# Breakouts2.net
KiCad netlist of a schematic drawn in EAGLE
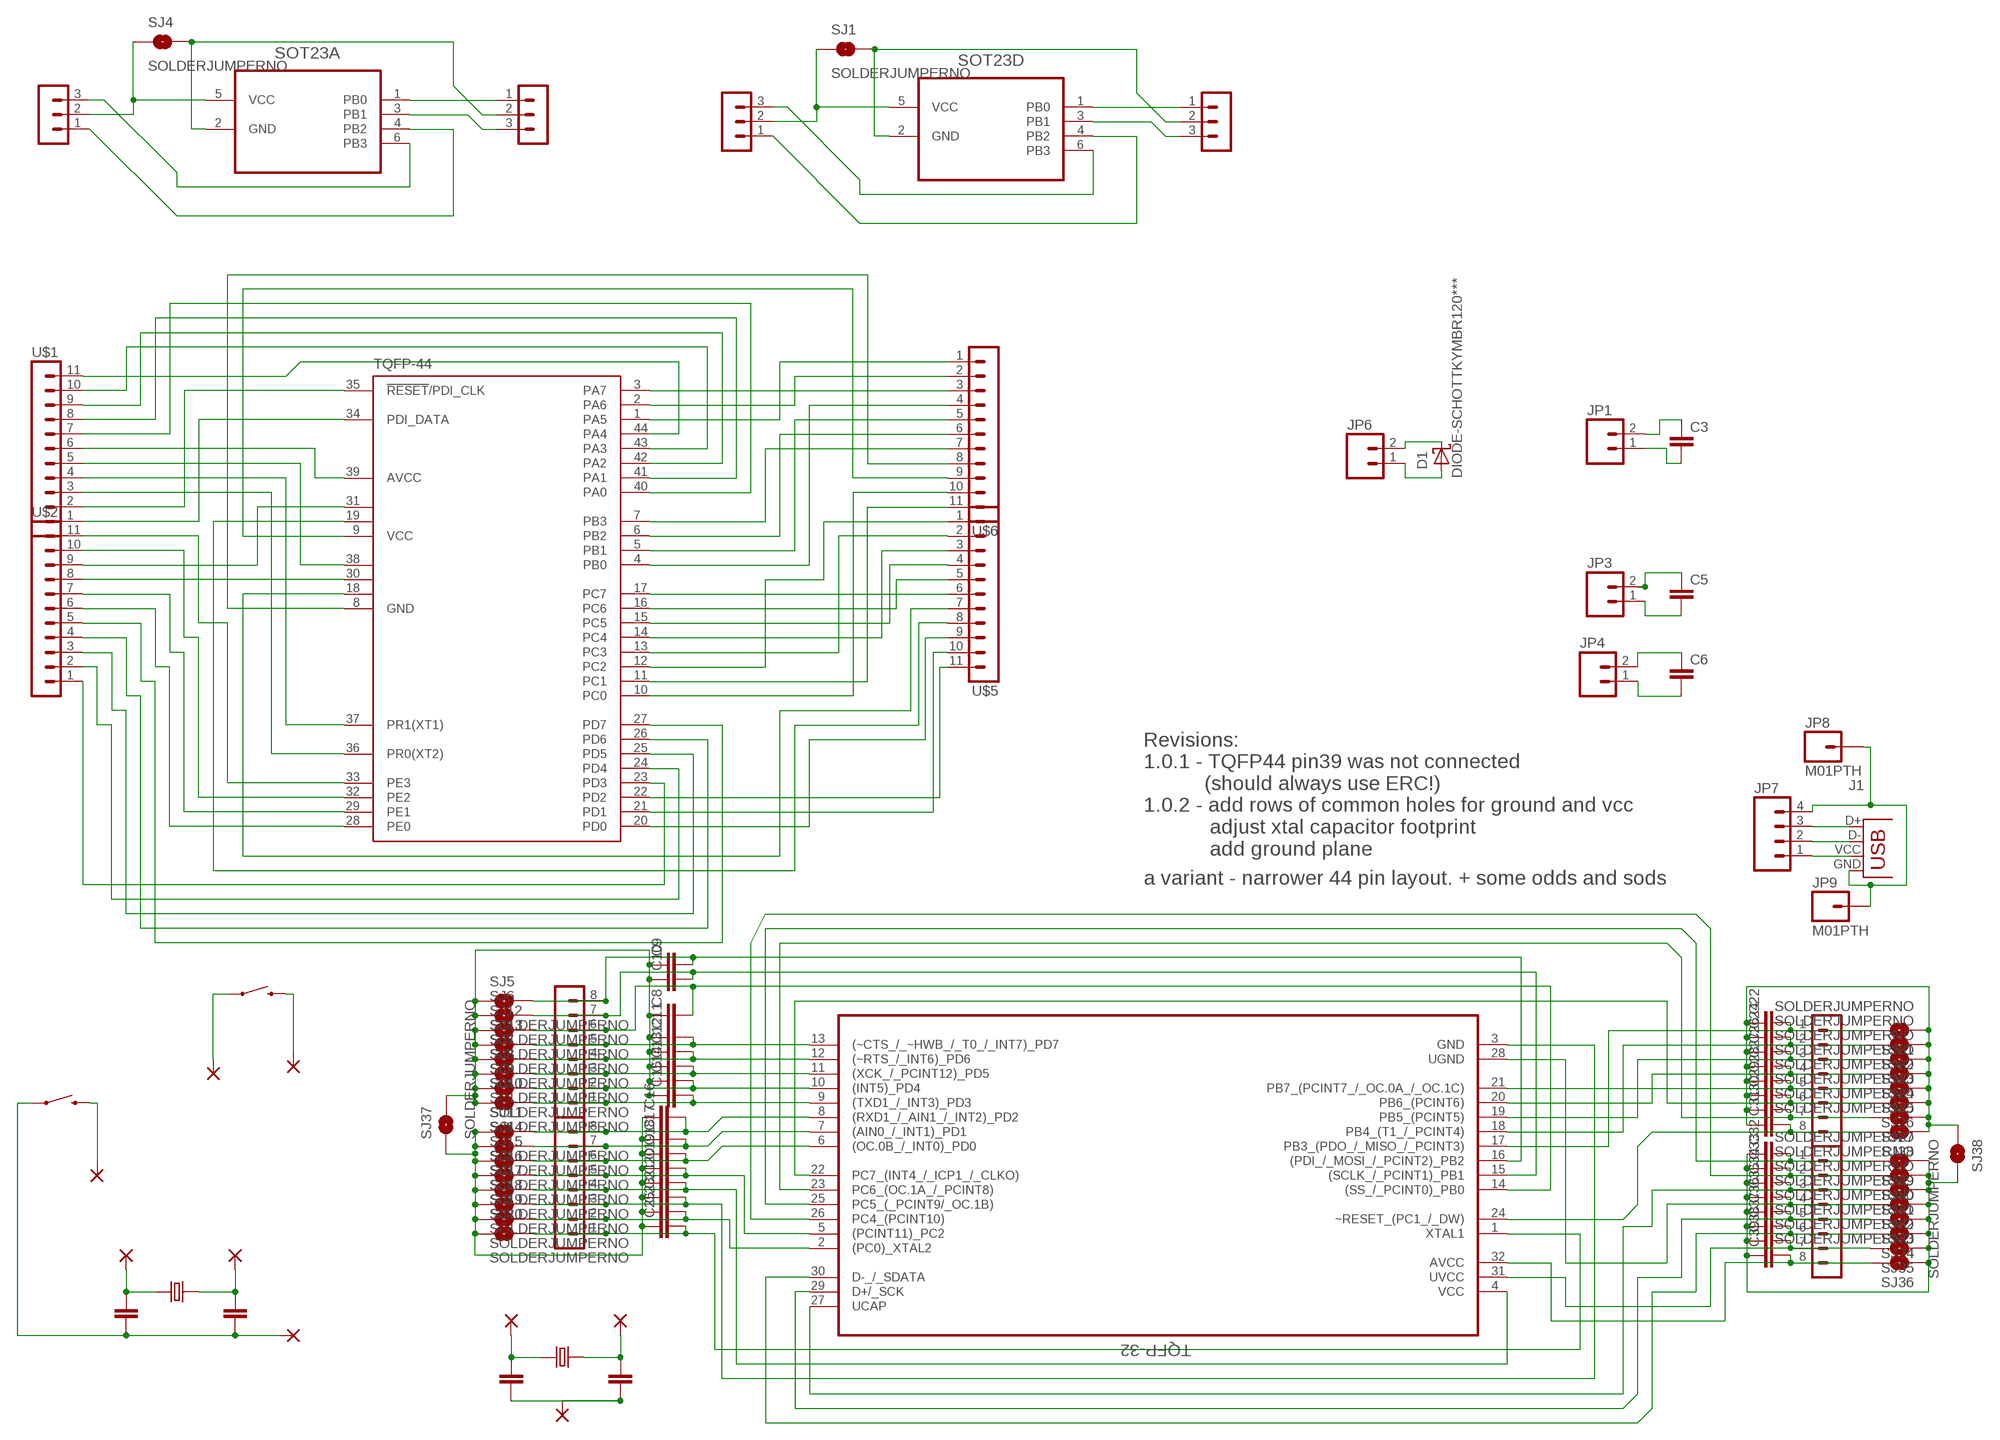
[diagram p0: schematic, sheet 1]

(export (version "E")
  (design (tool "Eeschema 10.0.6"))
  (components
    (comp (ref "C1")
      (value "C-EU025-024X044**100NF+22PF")
      (footprint "eagle-import:C025-024X044")
      (libsource (lib "eagle-import") (part "C-EU025-024X044100NF+22PF"))
    )
    (comp (ref "C2")
      (value "C-EU025-024X044**100NF+22PF")
      (footprint "eagle-import:C025-024X044")
      (libsource (lib "eagle-import") (part "C-EU025-024X044100NF+22PF"))
    )
    (comp (ref "C3")
      (value "C-EU1206")
      (footprint "eagle-import:1206")
      (libsource (lib "eagle-import") (part "C-EU1206"))
    )
    (comp (ref "C5")
      (value "C-EU1206")
      (footprint "eagle-import:1206")
      (libsource (lib "eagle-import") (part "C-EU1206"))
    )
    (comp (ref "C6")
      (value "C-EU1206")
      (footprint "eagle-import:1206")
      (libsource (lib "eagle-import") (part "C-EU1206"))
    )
    (comp (ref "C8")
      (value "C-EU1206")
      (footprint "eagle-import:1206")
      (libsource (lib "eagle-import") (part "C-EU1206"))
    )
    (comp (ref "C9")
      (value "C-EU1206")
      (footprint "eagle-import:1206")
      (libsource (lib "eagle-import") (part "C-EU1206"))
    )
    (comp (ref "C10")
      (value "C-EU1206")
      (footprint "eagle-import:1206")
      (libsource (lib "eagle-import") (part "C-EU1206"))
    )
    (comp (ref "C11")
      (value "C-EU1206")
      (footprint "eagle-import:1206")
      (libsource (lib "eagle-import") (part "C-EU1206"))
    )
    (comp (ref "C12")
      (value "C-EU1206")
      (footprint "eagle-import:1206")
      (libsource (lib "eagle-import") (part "C-EU1206"))
    )
    (comp (ref "C13")
      (value "C-EU1206")
      (footprint "eagle-import:1206")
      (libsource (lib "eagle-import") (part "C-EU1206"))
    )
    (comp (ref "C14")
      (value "C-EU1206")
      (footprint "eagle-import:1206")
      (libsource (lib "eagle-import") (part "C-EU1206"))
    )
    (comp (ref "C15")
      (value "C-EU1206")
      (footprint "eagle-import:1206")
      (libsource (lib "eagle-import") (part "C-EU1206"))
    )
    (comp (ref "C16")
      (value "C-EU1206")
      (footprint "eagle-import:1206")
      (libsource (lib "eagle-import") (part "C-EU1206"))
    )
    (comp (ref "C17")
      (value "C-EU1206")
      (footprint "eagle-import:1206")
      (libsource (lib "eagle-import") (part "C-EU1206"))
    )
    (comp (ref "C18")
      (value "C-EU1206")
      (footprint "eagle-import:1206")
      (libsource (lib "eagle-import") (part "C-EU1206"))
    )
    (comp (ref "C19")
      (value "C-EU1206")
      (footprint "eagle-import:1206")
      (libsource (lib "eagle-import") (part "C-EU1206"))
    )
    (comp (ref "C20")
      (value "C-EU1206")
      (footprint "eagle-import:1206")
      (libsource (lib "eagle-import") (part "C-EU1206"))
    )
    (comp (ref "C21")
      (value "C-EU1206")
      (footprint "eagle-import:1206")
      (libsource (lib "eagle-import") (part "C-EU1206"))
    )
    (comp (ref "C22")
      (value "C-EU1206")
      (footprint "eagle-import:1206")
      (libsource (lib "eagle-import") (part "C-EU1206"))
    )
    (comp (ref "C23")
      (value "C-EU1206")
      (footprint "eagle-import:1206")
      (libsource (lib "eagle-import") (part "C-EU1206"))
    )
    (comp (ref "C24")
      (value "C-EU1206")
      (footprint "eagle-import:1206")
      (libsource (lib "eagle-import") (part "C-EU1206"))
    )
    (comp (ref "C25")
      (value "C-EU1206")
      (footprint "eagle-import:1206")
      (libsource (lib "eagle-import") (part "C-EU1206"))
    )
    (comp (ref "C26")
      (value "C-EU1206")
      (footprint "eagle-import:1206")
      (libsource (lib "eagle-import") (part "C-EU1206"))
    )
    (comp (ref "C27")
      (value "C-EU1206")
      (footprint "eagle-import:1206")
      (libsource (lib "eagle-import") (part "C-EU1206"))
    )
    (comp (ref "C28")
      (value "C-EU1206")
      (footprint "eagle-import:1206")
      (libsource (lib "eagle-import") (part "C-EU1206"))
    )
    (comp (ref "C29")
      (value "C-EU1206")
      (footprint "eagle-import:1206")
      (libsource (lib "eagle-import") (part "C-EU1206"))
    )
    (comp (ref "C30")
      (value "C-EU1206")
      (footprint "eagle-import:1206")
      (libsource (lib "eagle-import") (part "C-EU1206"))
    )
    (comp (ref "C31")
      (value "C-EU1206")
      (footprint "eagle-import:1206")
      (libsource (lib "eagle-import") (part "C-EU1206"))
    )
    (comp (ref "C32")
      (value "C-EU1206")
      (footprint "eagle-import:1206")
      (libsource (lib "eagle-import") (part "C-EU1206"))
    )
    (comp (ref "C33")
      (value "C-EU1206")
      (footprint "eagle-import:1206")
      (libsource (lib "eagle-import") (part "C-EU1206"))
    )
    (comp (ref "C34")
      (value "C-EU1206")
      (footprint "eagle-import:1206")
      (libsource (lib "eagle-import") (part "C-EU1206"))
    )
    (comp (ref "C35")
      (value "C-EU1206")
      (footprint "eagle-import:1206")
      (libsource (lib "eagle-import") (part "C-EU1206"))
    )
    (comp (ref "C36")
      (value "C-EU1206")
      (footprint "eagle-import:1206")
      (libsource (lib "eagle-import") (part "C-EU1206"))
    )
    (comp (ref "C37")
      (value "C-EU1206")
      (footprint "eagle-import:1206")
      (libsource (lib "eagle-import") (part "C-EU1206"))
    )
    (comp (ref "C38")
      (value "C-EU1206")
      (footprint "eagle-import:1206")
      (libsource (lib "eagle-import") (part "C-EU1206"))
    )
    (comp (ref "C39")
      (value "C-EU1206")
      (footprint "eagle-import:1206")
      (libsource (lib "eagle-import") (part "C-EU1206"))
    )
    (comp (ref "C40")
      (value "C-EU025-024X044**100NF+22PF")
      (footprint "eagle-import:C025-024X044")
      (libsource (lib "eagle-import") (part "C-EU025-024X044100NF+22PF"))
    )
    (comp (ref "C41")
      (value "C-EU025-024X044**100NF+22PF")
      (footprint "eagle-import:C025-024X044")
      (libsource (lib "eagle-import") (part "C-EU025-024X044100NF+22PF"))
    )
    (comp (ref "D1")
      (value "DIODE-SCHOTTKYMBR120***")
      (footprint "eagle-import:SOD123")
      (libsource (lib "eagle-import") (part "DIODE-SCHOTTKYMBR120"))
    )
    (comp (ref "J1")
      (value "USB-FCI_SMD***")
      (footprint "eagle-import:FCI_USB_B_SMD")
      (libsource (lib "eagle-import") (part "USB-FCI_SMD"))
    )
    (comp (ref "JP1")
      (value "M02PTH")
      (footprint "eagle-import:1X02")
      (libsource (lib "eagle-import") (part "M02PTH"))
    )
    (comp (ref "JP3")
      (value "M02PTH")
      (footprint "eagle-import:1X02")
      (libsource (lib "eagle-import") (part "M02PTH"))
    )
    (comp (ref "JP4")
      (value "M02PTH")
      (footprint "eagle-import:1X02")
      (libsource (lib "eagle-import") (part "M02PTH"))
    )
    (comp (ref "JP6")
      (value "M02PTH")
      (footprint "eagle-import:1X02")
      (libsource (lib "eagle-import") (part "M02PTH"))
    )
    (comp (ref "JP7")
      (value "M04PTH")
      (footprint "eagle-import:1X04")
      (libsource (lib "eagle-import") (part "M04PTH"))
    )
    (comp (ref "JP8")
      (value "M01PTH")
      (footprint "eagle-import:1X01")
      (libsource (lib "eagle-import") (part "M01PTH"))
    )
    (comp (ref "JP9")
      (value "M01PTH")
      (footprint "eagle-import:1X01")
      (libsource (lib "eagle-import") (part "M01PTH"))
    )
    (comp (ref "PAD1")
      (value "WIREPAD1,6/0,8")
      (footprint "eagle-import:1,6_0,8")
      (libsource (lib "eagle-import") (part "WIREPAD1,6/0,8"))
    )
    (comp (ref "PAD2")
      (value "WIREPAD1,6/0,8")
      (footprint "eagle-import:1,6_0,8")
      (libsource (lib "eagle-import") (part "WIREPAD1,6/0,8"))
    )
    (comp (ref "PAD3")
      (value "WIREPAD1,6/0,8")
      (footprint "eagle-import:1,6_0,8")
      (libsource (lib "eagle-import") (part "WIREPAD1,6/0,8"))
    )
    (comp (ref "PAD4")
      (value "WIREPAD1,6/0,8")
      (footprint "eagle-import:1,6_0,8")
      (libsource (lib "eagle-import") (part "WIREPAD1,6/0,8"))
    )
    (comp (ref "PAD5")
      (value "WIREPAD1,6/0,8")
      (footprint "eagle-import:1,6_0,8")
      (libsource (lib "eagle-import") (part "WIREPAD1,6/0,8"))
    )
    (comp (ref "PAD6")
      (value "WIREPAD1,6/0,8")
      (footprint "eagle-import:1,6_0,8")
      (libsource (lib "eagle-import") (part "WIREPAD1,6/0,8"))
    )
    (comp (ref "PAD7")
      (value "WIREPAD1,6/0,8")
      (footprint "eagle-import:1,6_0,8")
      (libsource (lib "eagle-import") (part "WIREPAD1,6/0,8"))
    )
    (comp (ref "PAD8")
      (value "WIREPAD1,6/0,8")
      (footprint "eagle-import:1,6_0,8")
      (libsource (lib "eagle-import") (part "WIREPAD1,6/0,8"))
    )
    (comp (ref "PAD9")
      (value "WIREPAD1,6/0,8")
      (footprint "eagle-import:1,6_0,8")
      (libsource (lib "eagle-import") (part "WIREPAD1,6/0,8"))
    )
    (comp (ref "S1")
      (value "SWITCH-MOMENTARY-2PTH")
      (footprint "eagle-import:TACTILE-PTH")
      (libsource (lib "eagle-import") (part "SWITCH-MOMENTARY-2PTH"))
    )
    (comp (ref "S2")
      (value "SWITCH-MOMENTARY-2PTH")
      (footprint "eagle-import:TACTILE-PTH")
      (libsource (lib "eagle-import") (part "SWITCH-MOMENTARY-2PTH"))
    )
    (comp (ref "SJ1")
      (value "SOLDERJUMPERNO")
      (footprint "eagle-import:SJ_2S-NO")
      (libsource (lib "eagle-import") (part "SOLDERJUMPERNO"))
    )
    (comp (ref "SJ4")
      (value "SOLDERJUMPERNO")
      (footprint "eagle-import:SJ_2S-NO")
      (libsource (lib "eagle-import") (part "SOLDERJUMPERNO"))
    )
    (comp (ref "SJ5")
      (value "SOLDERJUMPERNO")
      (footprint "eagle-import:SJ_2S-NO")
      (libsource (lib "eagle-import") (part "SOLDERJUMPERNO"))
    )
    (comp (ref "SJ6")
      (value "SOLDERJUMPERNO")
      (footprint "eagle-import:SJ_2S-NO")
      (libsource (lib "eagle-import") (part "SOLDERJUMPERNO"))
    )
    (comp (ref "SJ7")
      (value "SOLDERJUMPERNO")
      (footprint "eagle-import:SJ_2S-NO")
      (libsource (lib "eagle-import") (part "SOLDERJUMPERNO"))
    )
    (comp (ref "SJ8")
      (value "SOLDERJUMPERNO")
      (footprint "eagle-import:SJ_2S-NO")
      (libsource (lib "eagle-import") (part "SOLDERJUMPERNO"))
    )
    (comp (ref "SJ9")
      (value "SOLDERJUMPERNO")
      (footprint "eagle-import:SJ_2S-NO")
      (libsource (lib "eagle-import") (part "SOLDERJUMPERNO"))
    )
    (comp (ref "SJ10")
      (value "SOLDERJUMPERNO")
      (footprint "eagle-import:SJ_2S-NO")
      (libsource (lib "eagle-import") (part "SOLDERJUMPERNO"))
    )
    (comp (ref "SJ11")
      (value "SOLDERJUMPERNO")
      (footprint "eagle-import:SJ_2S-NO")
      (libsource (lib "eagle-import") (part "SOLDERJUMPERNO"))
    )
    (comp (ref "SJ12")
      (value "SOLDERJUMPERNO")
      (footprint "eagle-import:SJ_2S-NO")
      (libsource (lib "eagle-import") (part "SOLDERJUMPERNO"))
    )
    (comp (ref "SJ13")
      (value "SOLDERJUMPERNO")
      (footprint "eagle-import:SJ_2S-NO")
      (libsource (lib "eagle-import") (part "SOLDERJUMPERNO"))
    )
    (comp (ref "SJ14")
      (value "SOLDERJUMPERNO")
      (footprint "eagle-import:SJ_2S-NO")
      (libsource (lib "eagle-import") (part "SOLDERJUMPERNO"))
    )
    (comp (ref "SJ15")
      (value "SOLDERJUMPERNO")
      (footprint "eagle-import:SJ_2S-NO")
      (libsource (lib "eagle-import") (part "SOLDERJUMPERNO"))
    )
    (comp (ref "SJ16")
      (value "SOLDERJUMPERNO")
      (footprint "eagle-import:SJ_2S-NO")
      (libsource (lib "eagle-import") (part "SOLDERJUMPERNO"))
    )
    (comp (ref "SJ17")
      (value "SOLDERJUMPERNO")
      (footprint "eagle-import:SJ_2S-NO")
      (libsource (lib "eagle-import") (part "SOLDERJUMPERNO"))
    )
    (comp (ref "SJ18")
      (value "SOLDERJUMPERNO")
      (footprint "eagle-import:SJ_2S-NO")
      (libsource (lib "eagle-import") (part "SOLDERJUMPERNO"))
    )
    (comp (ref "SJ19")
      (value "SOLDERJUMPERNO")
      (footprint "eagle-import:SJ_2S-NO")
      (libsource (lib "eagle-import") (part "SOLDERJUMPERNO"))
    )
    (comp (ref "SJ20")
      (value "SOLDERJUMPERNO")
      (footprint "eagle-import:SJ_2S-NO")
      (libsource (lib "eagle-import") (part "SOLDERJUMPERNO"))
    )
    (comp (ref "SJ21")
      (value "SOLDERJUMPERNO")
      (footprint "eagle-import:SJ_2S-NO")
      (libsource (lib "eagle-import") (part "SOLDERJUMPERNO"))
    )
    (comp (ref "SJ22")
      (value "SOLDERJUMPERNO")
      (footprint "eagle-import:SJ_2S-NO")
      (libsource (lib "eagle-import") (part "SOLDERJUMPERNO"))
    )
    (comp (ref "SJ23")
      (value "SOLDERJUMPERNO")
      (footprint "eagle-import:SJ_2S-NO")
      (libsource (lib "eagle-import") (part "SOLDERJUMPERNO"))
    )
    (comp (ref "SJ24")
      (value "SOLDERJUMPERNO")
      (footprint "eagle-import:SJ_2S-NO")
      (libsource (lib "eagle-import") (part "SOLDERJUMPERNO"))
    )
    (comp (ref "SJ25")
      (value "SOLDERJUMPERNO")
      (footprint "eagle-import:SJ_2S-NO")
      (libsource (lib "eagle-import") (part "SOLDERJUMPERNO"))
    )
    (comp (ref "SJ26")
      (value "SOLDERJUMPERNO")
      (footprint "eagle-import:SJ_2S-NO")
      (libsource (lib "eagle-import") (part "SOLDERJUMPERNO"))
    )
    (comp (ref "SJ27")
      (value "SOLDERJUMPERNO")
      (footprint "eagle-import:SJ_2S-NO")
      (libsource (lib "eagle-import") (part "SOLDERJUMPERNO"))
    )
    (comp (ref "SJ28")
      (value "SOLDERJUMPERNO")
      (footprint "eagle-import:SJ_2S-NO")
      (libsource (lib "eagle-import") (part "SOLDERJUMPERNO"))
    )
    (comp (ref "SJ29")
      (value "SOLDERJUMPERNO")
      (footprint "eagle-import:SJ_2S-NO")
      (libsource (lib "eagle-import") (part "SOLDERJUMPERNO"))
    )
    (comp (ref "SJ30")
      (value "SOLDERJUMPERNO")
      (footprint "eagle-import:SJ_2S-NO")
      (libsource (lib "eagle-import") (part "SOLDERJUMPERNO"))
    )
    (comp (ref "SJ31")
      (value "SOLDERJUMPERNO")
      (footprint "eagle-import:SJ_2S-NO")
      (libsource (lib "eagle-import") (part "SOLDERJUMPERNO"))
    )
    (comp (ref "SJ32")
      (value "SOLDERJUMPERNO")
      (footprint "eagle-import:SJ_2S-NO")
      (libsource (lib "eagle-import") (part "SOLDERJUMPERNO"))
    )
    (comp (ref "SJ33")
      (value "SOLDERJUMPERNO")
      (footprint "eagle-import:SJ_2S-NO")
      (libsource (lib "eagle-import") (part "SOLDERJUMPERNO"))
    )
    (comp (ref "SJ34")
      (value "SOLDERJUMPERNO")
      (footprint "eagle-import:SJ_2S-NO")
      (libsource (lib "eagle-import") (part "SOLDERJUMPERNO"))
    )
    (comp (ref "SJ35")
      (value "SOLDERJUMPERNO")
      (footprint "eagle-import:SJ_2S-NO")
      (libsource (lib "eagle-import") (part "SOLDERJUMPERNO"))
    )
    (comp (ref "SJ36")
      (value "SOLDERJUMPERNO")
      (footprint "eagle-import:SJ_2S-NO")
      (libsource (lib "eagle-import") (part "SOLDERJUMPERNO"))
    )
    (comp (ref "SJ37")
      (value "SOLDERJUMPERNO")
      (footprint "eagle-import:SJ_2S-NO")
      (libsource (lib "eagle-import") (part "SOLDERJUMPERNO"))
    )
    (comp (ref "SJ38")
      (value "SOLDERJUMPERNO")
      (footprint "eagle-import:SJ_2S-NO")
      (libsource (lib "eagle-import") (part "SOLDERJUMPERNO"))
    )
    (comp (ref "SOT23A")
      (value "ATTINY10-TSHR")
      (footprint "eagle-import:SOT95P280X145-6N")
      (libsource (lib "eagle-import") (part "ATTINY10-TSHR"))
    )
    (comp (ref "SOT23D")
      (value "ATTINY10-TSHR")
      (footprint "eagle-import:SOT95P280X145-6N")
      (libsource (lib "eagle-import") (part "ATTINY10-TSHR"))
    )
    (comp (ref "SV4")
      (value "MA08-1")
      (footprint "eagle-import:MA08-1")
      (libsource (lib "eagle-import") (part "MA08-1"))
    )
    (comp (ref "SV8")
      (value "MA08-1")
      (footprint "eagle-import:MA08-1")
      (libsource (lib "eagle-import") (part "MA08-1"))
    )
    (comp (ref "SV12")
      (value "MA03-1")
      (footprint "eagle-import:MA03-1")
      (libsource (lib "eagle-import") (part "MA03-1"))
    )
    (comp (ref "SV13")
      (value "MA03-1")
      (footprint "eagle-import:MA03-1")
      (libsource (lib "eagle-import") (part "MA03-1"))
    )
    (comp (ref "SV14")
      (value "MA03-1")
      (footprint "eagle-import:MA03-1")
      (libsource (lib "eagle-import") (part "MA03-1"))
    )
    (comp (ref "SV15")
      (value "MA03-1")
      (footprint "eagle-import:MA03-1")
      (libsource (lib "eagle-import") (part "MA03-1"))
    )
    (comp (ref "SV16")
      (value "MA08-1")
      (footprint "eagle-import:MA08-1")
      (libsource (lib "eagle-import") (part "MA08-1"))
    )
    (comp (ref "SV18")
      (value "MA08-1")
      (footprint "eagle-import:MA08-1")
      (libsource (lib "eagle-import") (part "MA08-1"))
    )
    (comp (ref "TQFP-32")
      (value "AT90USB162-16AU")
      (footprint "eagle-import:QFP80P900X900X120-32N")
      (libsource (lib "eagle-import") (part "AT90USB162-16AU"))
    )
    (comp (ref "TQFP-44")
      (value "XMEGA16A4A")
      (footprint "eagle-import:TQFP44")
      (libsource (lib "eagle-import") (part "XMEGA16A4A"))
    )
    (comp (ref "U$1")
      (value "MA11-1")
      (footprint "eagle-import:MA11-1S")
      (libsource (lib "eagle-import") (part "MA11-1"))
    )
    (comp (ref "U$2")
      (value "MA11-1")
      (footprint "eagle-import:MA11-1S")
      (libsource (lib "eagle-import") (part "MA11-1"))
    )
    (comp (ref "U$5")
      (value "MA11-1")
      (footprint "eagle-import:MA11-1S")
      (libsource (lib "eagle-import") (part "MA11-1"))
    )
    (comp (ref "U$6")
      (value "MA11-1")
      (footprint "eagle-import:MA11-1S")
      (libsource (lib "eagle-import") (part "MA11-1"))
    )
    (comp (ref "X1")
      (value "CRYSTAL-HC49U-V**16MHZ")
      (footprint "eagle-import:HC49U-V")
      (libsource (lib "eagle-import") (part "CRYSTAL-HC49U-V16MHZ"))
    )
    (comp (ref "X2")
      (value "CRYSTAL-HC49U-V**16MHZ")
      (footprint "eagle-import:HC49U-V")
      (libsource (lib "eagle-import") (part "CRYSTAL-HC49U-V16MHZ"))
    )
  )
  (nets
    (net (code "1") (name "Net-(C3-Pad1)") (class "Default")
      (node (ref "C3") (pin "1") (pinfunction "1_1") (pintype "passive"))
      (node (ref "JP1") (pin "2") (pinfunction "2_2") (pintype "passive"))
    )
    (net (code "2") (name "Net-(C3-Pad2)") (class "Default")
      (node (ref "C3") (pin "2") (pinfunction "2_2") (pintype "passive"))
      (node (ref "JP1") (pin "1") (pinfunction "1_1") (pintype "passive"))
    )
    (net (code "3") (name "Net-(C5-Pad1)") (class "Default")
      (node (ref "C5") (pin "1") (pinfunction "1_1") (pintype "passive"))
      (node (ref "JP3") (pin "2") (pinfunction "2_2") (pintype "passive"))
    )
    (net (code "4") (name "Net-(C5-Pad2)") (class "Default")
      (node (ref "C5") (pin "2") (pinfunction "2_2") (pintype "passive"))
      (node (ref "JP3") (pin "1") (pinfunction "1_1") (pintype "passive"))
    )
    (net (code "5") (name "Net-(C6-Pad1)") (class "Default")
      (node (ref "C6") (pin "1") (pinfunction "1_1") (pintype "passive"))
      (node (ref "JP4") (pin "2") (pinfunction "2_2") (pintype "passive"))
    )
    (net (code "6") (name "Net-(C6-Pad2)") (class "Default")
      (node (ref "C6") (pin "2") (pinfunction "2_2") (pintype "passive"))
      (node (ref "JP4") (pin "1") (pinfunction "1_1") (pintype "passive"))
    )
    (net (code "7") (name "Net-(C10-Pad1)") (class "Default")
      (node (ref "C10") (pin "1") (pinfunction "1_1") (pintype "passive"))
      (node (ref "C11") (pin "1") (pinfunction "1_1") (pintype "passive"))
      (node (ref "C12") (pin "1") (pinfunction "1_1") (pintype "passive"))
      (node (ref "C13") (pin "1") (pinfunction "1_1") (pintype "passive"))
      (node (ref "C14") (pin "1") (pinfunction "1_1") (pintype "passive"))
      (node (ref "C15") (pin "1") (pinfunction "1_1") (pintype "passive"))
      (node (ref "C8") (pin "1") (pinfunction "1_1") (pintype "passive"))
      (node (ref "C9") (pin "1") (pinfunction "1_1") (pintype "passive"))
      (node (ref "SJ10") (pin "1") (pinfunction "1_1") (pintype "passive"))
      (node (ref "SJ12") (pin "1") (pinfunction "1_1") (pintype "passive"))
      (node (ref "SJ13") (pin "1") (pinfunction "1_1") (pintype "passive"))
      (node (ref "SJ37") (pin "2") (pinfunction "2_2") (pintype "passive"))
      (node (ref "SJ5") (pin "1") (pinfunction "1_1") (pintype "passive"))
      (node (ref "SJ6") (pin "1") (pinfunction "1_1") (pintype "passive"))
      (node (ref "SJ7") (pin "1") (pinfunction "1_1") (pintype "passive"))
      (node (ref "SJ8") (pin "1") (pinfunction "1_1") (pintype "passive"))
      (node (ref "SJ9") (pin "1") (pinfunction "1_1") (pintype "passive"))
    )
    (net (code "8") (name "Net-(C16-Pad1)") (class "Default")
      (node (ref "C16") (pin "1") (pinfunction "1_1") (pintype "passive"))
      (node (ref "C17") (pin "1") (pinfunction "1_1") (pintype "passive"))
      (node (ref "C18") (pin "1") (pinfunction "1_1") (pintype "passive"))
      (node (ref "C19") (pin "1") (pinfunction "1_1") (pintype "passive"))
      (node (ref "C20") (pin "1") (pinfunction "1_1") (pintype "passive"))
      (node (ref "C21") (pin "1") (pinfunction "1_1") (pintype "passive"))
      (node (ref "C23") (pin "1") (pinfunction "1_1") (pintype "passive"))
      (node (ref "C25") (pin "1") (pinfunction "1_1") (pintype "passive"))
      (node (ref "SJ11") (pin "1") (pinfunction "1_1") (pintype "passive"))
      (node (ref "SJ14") (pin "1") (pinfunction "1_1") (pintype "passive"))
      (node (ref "SJ15") (pin "1") (pinfunction "1_1") (pintype "passive"))
      (node (ref "SJ16") (pin "1") (pinfunction "1_1") (pintype "passive"))
      (node (ref "SJ17") (pin "1") (pinfunction "1_1") (pintype "passive"))
      (node (ref "SJ18") (pin "1") (pinfunction "1_1") (pintype "passive"))
      (node (ref "SJ19") (pin "1") (pinfunction "1_1") (pintype "passive"))
      (node (ref "SJ20") (pin "1") (pinfunction "1_1") (pintype "passive"))
      (node (ref "SJ37") (pin "1") (pinfunction "1_1") (pintype "passive"))
    )
    (net (code "9") (name "Net-(C22-Pad1)") (class "Default")
      (node (ref "C22") (pin "1") (pinfunction "1_1") (pintype "passive"))
      (node (ref "C24") (pin "1") (pinfunction "1_1") (pintype "passive"))
      (node (ref "C26") (pin "1") (pinfunction "1_1") (pintype "passive"))
      (node (ref "C27") (pin "1") (pinfunction "1_1") (pintype "passive"))
      (node (ref "C28") (pin "1") (pinfunction "1_1") (pintype "passive"))
      (node (ref "C29") (pin "1") (pinfunction "1_1") (pintype "passive"))
      (node (ref "C30") (pin "1") (pinfunction "1_1") (pintype "passive"))
      (node (ref "C31") (pin "1") (pinfunction "1_1") (pintype "passive"))
      (node (ref "SJ21") (pin "1") (pinfunction "1_1") (pintype "passive"))
      (node (ref "SJ22") (pin "1") (pinfunction "1_1") (pintype "passive"))
      (node (ref "SJ23") (pin "1") (pinfunction "1_1") (pintype "passive"))
      (node (ref "SJ24") (pin "1") (pinfunction "1_1") (pintype "passive"))
      (node (ref "SJ25") (pin "1") (pinfunction "1_1") (pintype "passive"))
      (node (ref "SJ26") (pin "1") (pinfunction "1_1") (pintype "passive"))
      (node (ref "SJ27") (pin "1") (pinfunction "1_1") (pintype "passive"))
      (node (ref "SJ28") (pin "1") (pinfunction "1_1") (pintype "passive"))
      (node (ref "SJ38") (pin "1") (pinfunction "1_1") (pintype "passive"))
    )
    (net (code "10") (name "Net-(C32-Pad1)") (class "Default")
      (node (ref "C32") (pin "1") (pinfunction "1_1") (pintype "passive"))
      (node (ref "C33") (pin "1") (pinfunction "1_1") (pintype "passive"))
      (node (ref "C34") (pin "1") (pinfunction "1_1") (pintype "passive"))
      (node (ref "C35") (pin "1") (pinfunction "1_1") (pintype "passive"))
      (node (ref "C36") (pin "1") (pinfunction "1_1") (pintype "passive"))
      (node (ref "C37") (pin "1") (pinfunction "1_1") (pintype "passive"))
      (node (ref "C38") (pin "1") (pinfunction "1_1") (pintype "passive"))
      (node (ref "C39") (pin "1") (pinfunction "1_1") (pintype "passive"))
      (node (ref "SJ29") (pin "1") (pinfunction "1_1") (pintype "passive"))
      (node (ref "SJ30") (pin "1") (pinfunction "1_1") (pintype "passive"))
      (node (ref "SJ31") (pin "1") (pinfunction "1_1") (pintype "passive"))
      (node (ref "SJ32") (pin "1") (pinfunction "1_1") (pintype "passive"))
      (node (ref "SJ33") (pin "1") (pinfunction "1_1") (pintype "passive"))
      (node (ref "SJ34") (pin "1") (pinfunction "1_1") (pintype "passive"))
      (node (ref "SJ35") (pin "1") (pinfunction "1_1") (pintype "passive"))
      (node (ref "SJ36") (pin "1") (pinfunction "1_1") (pintype "passive"))
      (node (ref "SJ38") (pin "2") (pinfunction "2_2") (pintype "passive"))
    )
    (net (code "11") (name "Net-(D1-C)") (class "Default")
      (node (ref "D1") (pin "K") (pinfunction "C_K") (pintype "passive"))
      (node (ref "JP6") (pin "2") (pinfunction "2_2") (pintype "passive"))
    )
    (net (code "12") (name "Net-(D1-PadA)") (class "Default")
      (node (ref "D1") (pin "A") (pinfunction "A_A") (pintype "passive"))
      (node (ref "JP6") (pin "1") (pinfunction "1_1") (pintype "passive"))
    )
    (net (code "13") (name "Net-(J1-PadD+)") (class "Default")
      (node (ref "J1") (pin "D+") (pinfunction "D+_D+") (pintype "bidirectional"))
      (node (ref "JP7") (pin "3") (pinfunction "3_3") (pintype "passive"))
    )
    (net (code "14") (name "Net-(J1-PadD-)") (class "Default")
      (node (ref "J1") (pin "D-") (pinfunction "D-_D-") (pintype "bidirectional"))
      (node (ref "JP7") (pin "2") (pinfunction "2_2") (pintype "passive"))
    )
    (net (code "15") (name "Net-(J1-PadGND)") (class "Default")
      (node (ref "J1") (pin "GND") (pinfunction "GND_GND") (pintype "bidirectional"))
      (node (ref "JP7") (pin "4") (pinfunction "4_4") (pintype "passive"))
      (node (ref "JP8") (pin "1") (pinfunction "1_1") (pintype "passive"))
      (node (ref "JP9") (pin "1") (pinfunction "1_1") (pintype "passive"))
    )
    (net (code "16") (name "Net-(J1-VBUS)") (class "Default")
      (node (ref "J1") (pin "VCC") (pinfunction "VBUS_VCC") (pintype "bidirectional"))
      (node (ref "JP7") (pin "1") (pinfunction "1_1") (pintype "passive"))
    )
    (net (code "17") (name "Net-(PAD1-P)") (class "Default")
      (node (ref "PAD1") (pin "1") (pinfunction "P_1") (pintype "passive"))
      (node (ref "S1") (pin "3") (pinfunction "2_3") (pintype "passive"))
    )
    (net (code "18") (name "Net-(PAD2-P)") (class "Default")
      (node (ref "C41") (pin "1") (pinfunction "1_1") (pintype "passive"))
      (node (ref "PAD2") (pin "1") (pinfunction "P_1") (pintype "passive"))
      (node (ref "X2") (pin "1") (pinfunction "1_1") (pintype "passive"))
    )
    (net (code "19") (name "Net-(PAD3-P)") (class "Default")
      (node (ref "PAD3") (pin "1") (pinfunction "P_1") (pintype "passive"))
      (node (ref "S2") (pin "3") (pinfunction "2_3") (pintype "passive"))
    )
    (net (code "20") (name "Net-(PAD4-P)") (class "Default")
      (node (ref "PAD4") (pin "1") (pinfunction "P_1") (pintype "passive"))
      (node (ref "S2") (pin "1") (pinfunction "1_1") (pintype "passive"))
    )
    (net (code "21") (name "Net-(PAD5-P)") (class "Default")
      (node (ref "C40") (pin "1") (pinfunction "1_1") (pintype "passive"))
      (node (ref "PAD5") (pin "1") (pinfunction "P_1") (pintype "passive"))
      (node (ref "X2") (pin "2") (pinfunction "2_2") (pintype "passive"))
    )
    (net (code "22") (name "Net-(PAD6-P)") (class "Default")
      (node (ref "C2") (pin "1") (pinfunction "1_1") (pintype "passive"))
      (node (ref "PAD6") (pin "1") (pinfunction "P_1") (pintype "passive"))
      (node (ref "X1") (pin "1") (pinfunction "1_1") (pintype "passive"))
    )
    (net (code "23") (name "Net-(PAD7-P)") (class "Default")
      (node (ref "C1") (pin "1") (pinfunction "1_1") (pintype "passive"))
      (node (ref "PAD7") (pin "1") (pinfunction "P_1") (pintype "passive"))
      (node (ref "X1") (pin "2") (pinfunction "2_2") (pintype "passive"))
    )
    (net (code "24") (name "Net-(PAD8-P)") (class "Default")
      (node (ref "C1") (pin "2") (pinfunction "2_2") (pintype "passive"))
      (node (ref "C2") (pin "2") (pinfunction "2_2") (pintype "passive"))
      (node (ref "PAD8") (pin "1") (pinfunction "P_1") (pintype "passive"))
      (node (ref "S1") (pin "1") (pinfunction "1_1") (pintype "passive"))
    )
    (net (code "25") (name "Net-(PAD9-P)") (class "Default")
      (node (ref "C40") (pin "2") (pinfunction "2_2") (pintype "passive"))
      (node (ref "C41") (pin "2") (pinfunction "2_2") (pintype "passive"))
      (node (ref "PAD9") (pin "1") (pinfunction "P_1") (pintype "passive"))
    )
    (net (code "26") (name "Net-(SOT23A-GND)") (class "Default")
      (node (ref "SJ4") (pin "2") (pinfunction "2_2") (pintype "passive"))
      (node (ref "SOT23A") (pin "2") (pinfunction "GND_2") (pintype "passive"))
      (node (ref "SV15") (pin "2") (pinfunction "2_2") (pintype "passive"))
    )
    (net (code "27") (name "Net-(SOT23A-PB0)") (class "Default")
      (node (ref "SOT23A") (pin "1") (pinfunction "PB0_1") (pintype "bidirectional"))
      (node (ref "SV15") (pin "1") (pinfunction "1_1") (pintype "passive"))
    )
    (net (code "28") (name "Net-(SOT23A-PB1)") (class "Default")
      (node (ref "SOT23A") (pin "3") (pinfunction "PB1_3") (pintype "bidirectional"))
      (node (ref "SV15") (pin "3") (pinfunction "3_3") (pintype "passive"))
    )
    (net (code "29") (name "Net-(SOT23A-PB2)") (class "Default")
      (node (ref "SOT23A") (pin "4") (pinfunction "PB2_4") (pintype "bidirectional"))
      (node (ref "SV14") (pin "1") (pinfunction "1_1") (pintype "passive"))
    )
    (net (code "30") (name "Net-(SOT23A-PB3)") (class "Default")
      (node (ref "SOT23A") (pin "6") (pinfunction "PB3_6") (pintype "bidirectional"))
      (node (ref "SV14") (pin "3") (pinfunction "3_3") (pintype "passive"))
    )
    (net (code "31") (name "Net-(SOT23A-VCC)") (class "Default")
      (node (ref "SJ4") (pin "1") (pinfunction "1_1") (pintype "passive"))
      (node (ref "SOT23A") (pin "5") (pinfunction "VCC_5") (pintype "power_in"))
      (node (ref "SV14") (pin "2") (pinfunction "2_2") (pintype "passive"))
    )
    (net (code "32") (name "Net-(SOT23D-GND)") (class "Default")
      (node (ref "SJ1") (pin "2") (pinfunction "2_2") (pintype "passive"))
      (node (ref "SOT23D") (pin "2") (pinfunction "GND_2") (pintype "passive"))
      (node (ref "SV13") (pin "2") (pinfunction "2_2") (pintype "passive"))
    )
    (net (code "33") (name "Net-(SOT23D-PB0)") (class "Default")
      (node (ref "SOT23D") (pin "1") (pinfunction "PB0_1") (pintype "bidirectional"))
      (node (ref "SV13") (pin "1") (pinfunction "1_1") (pintype "passive"))
    )
    (net (code "34") (name "Net-(SOT23D-PB1)") (class "Default")
      (node (ref "SOT23D") (pin "3") (pinfunction "PB1_3") (pintype "bidirectional"))
      (node (ref "SV13") (pin "3") (pinfunction "3_3") (pintype "passive"))
    )
    (net (code "35") (name "Net-(SOT23D-PB2)") (class "Default")
      (node (ref "SOT23D") (pin "4") (pinfunction "PB2_4") (pintype "bidirectional"))
      (node (ref "SV12") (pin "1") (pinfunction "1_1") (pintype "passive"))
    )
    (net (code "36") (name "Net-(SOT23D-PB3)") (class "Default")
      (node (ref "SOT23D") (pin "6") (pinfunction "PB3_6") (pintype "bidirectional"))
      (node (ref "SV12") (pin "3") (pinfunction "3_3") (pintype "passive"))
    )
    (net (code "37") (name "Net-(SOT23D-VCC)") (class "Default")
      (node (ref "SJ1") (pin "1") (pinfunction "1_1") (pintype "passive"))
      (node (ref "SOT23D") (pin "5") (pinfunction "VCC_5") (pintype "power_in"))
      (node (ref "SV12") (pin "2") (pinfunction "2_2") (pintype "passive"))
    )
    (net (code "38") (name "Net-(TQFP-32-(AIN0_{slash}_INT1)_PD1)") (class "Default")
      (node (ref "C17") (pin "2") (pinfunction "2_2") (pintype "passive"))
      (node (ref "SJ14") (pin "2") (pinfunction "2_2") (pintype "passive"))
      (node (ref "SV16") (pin "7") (pinfunction "7_7") (pintype "passive"))
      (node (ref "TQFP-32") (pin "7") (pinfunction "(AIN0_/_INT1)_PD1_7") (pintype "bidirectional"))
    )
    (net (code "39") (name "Net-(TQFP-32-(INT5)_PD4)") (class "Default")
      (node (ref "C14") (pin "2") (pinfunction "2_2") (pintype "passive"))
      (node (ref "SJ9") (pin "2") (pinfunction "2_2") (pintype "passive"))
      (node (ref "SV18") (pin "2") (pinfunction "2_2") (pintype "passive"))
      (node (ref "TQFP-32") (pin "10") (pinfunction "(INT5)_PD4_10") (pintype "bidirectional"))
    )
    (net (code "40") (name "Net-(TQFP-32-(OC.0B_{slash}_INT0)_PD0)") (class "Default")
      (node (ref "C18") (pin "2") (pinfunction "2_2") (pintype "passive"))
      (node (ref "SJ15") (pin "2") (pinfunction "2_2") (pintype "passive"))
      (node (ref "SV16") (pin "6") (pinfunction "6_6") (pintype "passive"))
      (node (ref "TQFP-32") (pin "6") (pinfunction "(OC.0B_/_INT0)_PD0_6") (pintype "bidirectional"))
    )
    (net (code "41") (name "Net-(TQFP-32-(PC0)_XTAL2)") (class "Default")
      (node (ref "C23") (pin "2") (pinfunction "2_2") (pintype "passive"))
      (node (ref "SJ19") (pin "2") (pinfunction "2_2") (pintype "passive"))
      (node (ref "SV16") (pin "2") (pinfunction "2_2") (pintype "passive"))
      (node (ref "TQFP-32") (pin "2") (pinfunction "(PC0)_XTAL2_2") (pintype "bidirectional"))
    )
    (net (code "42") (name "Net-(TQFP-32-(PCINT11)_PC2)") (class "Default")
      (node (ref "C19") (pin "2") (pinfunction "2_2") (pintype "passive"))
      (node (ref "SJ16") (pin "2") (pinfunction "2_2") (pintype "passive"))
      (node (ref "SV16") (pin "5") (pinfunction "5_5") (pintype "passive"))
      (node (ref "TQFP-32") (pin "5") (pinfunction "(PCINT11)_PC2_5") (pintype "bidirectional"))
    )
    (net (code "43") (name "Net-(TQFP-32-(PDI_{slash}_MOSI_{slash}_PCINT2)_PB2)") (class "Default")
      (node (ref "C9") (pin "2") (pinfunction "2_2") (pintype "passive"))
      (node (ref "SJ5") (pin "2") (pinfunction "2_2") (pintype "passive"))
      (node (ref "SV18") (pin "8") (pinfunction "8_8") (pintype "passive"))
      (node (ref "TQFP-32") (pin "16") (pinfunction "(PDI_/_MOSI_/_PCINT2)_PB2_16") (pintype "bidirectional"))
    )
    (net (code "44") (name "Net-(TQFP-32-(RXD1_{slash}_AIN1_{slash}_INT2)_PD2)") (class "Default")
      (node (ref "C16") (pin "2") (pinfunction "2_2") (pintype "passive"))
      (node (ref "SJ11") (pin "2") (pinfunction "2_2") (pintype "passive"))
      (node (ref "SV16") (pin "8") (pinfunction "8_8") (pintype "passive"))
      (node (ref "TQFP-32") (pin "8") (pinfunction "(RXD1_/_AIN1_/_INT2)_PD2_8") (pintype "bidirectional"))
    )
    (net (code "45") (name "Net-(TQFP-32-(SCLK_{slash}_PCINT1)_PB1)") (class "Default")
      (node (ref "C10") (pin "2") (pinfunction "2_2") (pintype "passive"))
      (node (ref "SJ6") (pin "2") (pinfunction "2_2") (pintype "passive"))
      (node (ref "SV18") (pin "7") (pinfunction "7_7") (pintype "passive"))
      (node (ref "TQFP-32") (pin "15") (pinfunction "(SCLK_/_PCINT1)_PB1_15") (pintype "bidirectional"))
    )
    (net (code "46") (name "Net-(TQFP-32-(SS_{slash}_PCINT0)_PB0)") (class "Default")
      (node (ref "C8") (pin "2") (pinfunction "2_2") (pintype "passive"))
      (node (ref "SJ12") (pin "2") (pinfunction "2_2") (pintype "passive"))
      (node (ref "SV18") (pin "6") (pinfunction "6_6") (pintype "passive"))
      (node (ref "TQFP-32") (pin "14") (pinfunction "(SS_/_PCINT0)_PB0_14") (pintype "bidirectional"))
    )
    (net (code "47") (name "Net-(TQFP-32-(TXD1_{slash}_INT3)_PD3)") (class "Default")
      (node (ref "C15") (pin "2") (pinfunction "2_2") (pintype "passive"))
      (node (ref "SJ10") (pin "2") (pinfunction "2_2") (pintype "passive"))
      (node (ref "SV18") (pin "1") (pinfunction "1_1") (pintype "passive"))
      (node (ref "TQFP-32") (pin "9") (pinfunction "(TXD1_/_INT3)_PD3_9") (pintype "bidirectional"))
    )
    (net (code "48") (name "Net-(TQFP-32-(XCK_{slash}_PCINT12)_PD5)") (class "Default")
      (node (ref "C13") (pin "2") (pinfunction "2_2") (pintype "passive"))
      (node (ref "SJ8") (pin "2") (pinfunction "2_2") (pintype "passive"))
      (node (ref "SV18") (pin "3") (pinfunction "3_3") (pintype "passive"))
      (node (ref "TQFP-32") (pin "11") (pinfunction "(XCK_/_PCINT12)_PD5_11") (pintype "bidirectional"))
    )
    (net (code "49") (name "Net-(TQFP-32-(~{CTS_{slash}_}HWB_{slash}_T0_{slash}_INT7)_PD7)") (class "Default")
      (node (ref "C11") (pin "2") (pinfunction "2_2") (pintype "passive"))
      (node (ref "SJ13") (pin "2") (pinfunction "2_2") (pintype "passive"))
      (node (ref "SV18") (pin "5") (pinfunction "5_5") (pintype "passive"))
      (node (ref "TQFP-32") (pin "13") (pinfunction "(~{CTS_/_}HWB_/_T0_/_INT7)_PD7_13") (pintype "bidirectional"))
    )
    (net (code "50") (name "Net-(TQFP-32-(~{RTS_{slash}_INT6})_PD6)") (class "Default")
      (node (ref "C12") (pin "2") (pinfunction "2_2") (pintype "passive"))
      (node (ref "SJ7") (pin "2") (pinfunction "2_2") (pintype "passive"))
      (node (ref "SV18") (pin "4") (pinfunction "4_4") (pintype "passive"))
      (node (ref "TQFP-32") (pin "12") (pinfunction "(~{RTS_/_INT6})_PD6_12") (pintype "bidirectional"))
    )
    (net (code "51") (name "Net-(TQFP-32-AVCC)") (class "Default")
      (node (ref "C39") (pin "2") (pinfunction "2_2") (pintype "passive"))
      (node (ref "SJ36") (pin "2") (pinfunction "2_2") (pintype "passive"))
      (node (ref "SV8") (pin "8") (pinfunction "8_8") (pintype "passive"))
      (node (ref "TQFP-32") (pin "32") (pinfunction "AVCC_32") (pintype "power_in"))
    )
    (net (code "52") (name "Net-(TQFP-32-D+{slash}_SCK)") (class "Default")
      (node (ref "C36") (pin "2") (pinfunction "2_2") (pintype "passive"))
      (node (ref "SJ33") (pin "2") (pinfunction "2_2") (pintype "passive"))
      (node (ref "SV8") (pin "5") (pinfunction "5_5") (pintype "passive"))
      (node (ref "TQFP-32") (pin "29") (pinfunction "D+/_SCK_29") (pintype "bidirectional"))
    )
    (net (code "53") (name "Net-(TQFP-32-D-_{slash}_SDATA)") (class "Default")
      (node (ref "C37") (pin "2") (pinfunction "2_2") (pintype "passive"))
      (node (ref "SJ34") (pin "2") (pinfunction "2_2") (pintype "passive"))
      (node (ref "SV8") (pin "6") (pinfunction "6_6") (pintype "passive"))
      (node (ref "TQFP-32") (pin "30") (pinfunction "D-_/_SDATA_30") (pintype "bidirectional"))
    )
    (net (code "54") (name "Net-(TQFP-32-GND)") (class "Default")
      (node (ref "C21") (pin "2") (pinfunction "2_2") (pintype "passive"))
      (node (ref "SJ18") (pin "2") (pinfunction "2_2") (pintype "passive"))
      (node (ref "SV16") (pin "3") (pinfunction "3_3") (pintype "passive"))
      (node (ref "TQFP-32") (pin "3") (pinfunction "GND_3") (pintype "passive"))
    )
    (net (code "55") (name "Net-(TQFP-32-PB3_(PDO_{slash}_MISO_{slash}_PCINT3))") (class "Default")
      (node (ref "C22") (pin "2") (pinfunction "2_2") (pintype "passive"))
      (node (ref "SJ21") (pin "2") (pinfunction "2_2") (pintype "passive"))
      (node (ref "SV4") (pin "1") (pinfunction "1_1") (pintype "passive"))
      (node (ref "TQFP-32") (pin "17") (pinfunction "PB3_(PDO_/_MISO_/_PCINT3)_17") (pintype "bidirectional"))
    )
    (net (code "56") (name "Net-(TQFP-32-PB4_(T1_{slash}_PCINT4))") (class "Default")
      (node (ref "C24") (pin "2") (pinfunction "2_2") (pintype "passive"))
      (node (ref "SJ22") (pin "2") (pinfunction "2_2") (pintype "passive"))
      (node (ref "SV4") (pin "2") (pinfunction "2_2") (pintype "passive"))
      (node (ref "TQFP-32") (pin "18") (pinfunction "PB4_(T1_/_PCINT4)_18") (pintype "bidirectional"))
    )
    (net (code "57") (name "Net-(TQFP-32-PB5_(PCINT5))") (class "Default")
      (node (ref "C26") (pin "2") (pinfunction "2_2") (pintype "passive"))
      (node (ref "SJ23") (pin "2") (pinfunction "2_2") (pintype "passive"))
      (node (ref "SV4") (pin "3") (pinfunction "3_3") (pintype "passive"))
      (node (ref "TQFP-32") (pin "19") (pinfunction "PB5_(PCINT5)_19") (pintype "bidirectional"))
    )
    (net (code "58") (name "Net-(TQFP-32-PB6_(PCINT6))") (class "Default")
      (node (ref "C27") (pin "2") (pinfunction "2_2") (pintype "passive"))
      (node (ref "SJ24") (pin "2") (pinfunction "2_2") (pintype "passive"))
      (node (ref "SV4") (pin "4") (pinfunction "4_4") (pintype "passive"))
      (node (ref "TQFP-32") (pin "20") (pinfunction "PB6_(PCINT6)_20") (pintype "bidirectional"))
    )
    (net (code "59") (name "Net-(TQFP-32-PB7_(PCINT7_{slash}_OC.0A_{slash}_OC.1C))") (class "Default")
      (node (ref "C28") (pin "2") (pinfunction "2_2") (pintype "passive"))
      (node (ref "SJ25") (pin "2") (pinfunction "2_2") (pintype "passive"))
      (node (ref "SV4") (pin "5") (pinfunction "5_5") (pintype "passive"))
      (node (ref "TQFP-32") (pin "21") (pinfunction "PB7_(PCINT7_/_OC.0A_/_OC.1C)_21") (pintype "bidirectional"))
    )
    (net (code "60") (name "Net-(TQFP-32-PC4_(PCINT10))") (class "Default")
      (node (ref "C33") (pin "2") (pinfunction "2_2") (pintype "passive"))
      (node (ref "SJ30") (pin "2") (pinfunction "2_2") (pintype "passive"))
      (node (ref "SV8") (pin "2") (pinfunction "2_2") (pintype "passive"))
      (node (ref "TQFP-32") (pin "26") (pinfunction "PC4_(PCINT10)_26") (pintype "bidirectional"))
    )
    (net (code "61") (name "Net-(TQFP-32-PC5_(_PCINT9{slash}_OC.1B))") (class "Default")
      (node (ref "C32") (pin "2") (pinfunction "2_2") (pintype "passive"))
      (node (ref "SJ29") (pin "2") (pinfunction "2_2") (pintype "passive"))
      (node (ref "SV8") (pin "1") (pinfunction "1_1") (pintype "passive"))
      (node (ref "TQFP-32") (pin "25") (pinfunction "PC5_(_PCINT9/_OC.1B)_25") (pintype "bidirectional"))
    )
    (net (code "62") (name "Net-(TQFP-32-PC6_(OC.1A_{slash}_PCINT8))") (class "Default")
      (node (ref "C30") (pin "2") (pinfunction "2_2") (pintype "passive"))
      (node (ref "SJ27") (pin "2") (pinfunction "2_2") (pintype "passive"))
      (node (ref "SV4") (pin "7") (pinfunction "7_7") (pintype "passive"))
      (node (ref "TQFP-32") (pin "23") (pinfunction "PC6_(OC.1A_/_PCINT8)_23") (pintype "bidirectional"))
    )
    (net (code "63") (name "Net-(TQFP-32-PC7_(INT4_{slash}_ICP1_{slash}_CLKO))") (class "Default")
      (node (ref "C29") (pin "2") (pinfunction "2_2") (pintype "passive"))
      (node (ref "SJ26") (pin "2") (pinfunction "2_2") (pintype "passive"))
      (node (ref "SV4") (pin "6") (pinfunction "6_6") (pintype "passive"))
      (node (ref "TQFP-32") (pin "22") (pinfunction "PC7_(INT4_/_ICP1_/_CLKO)_22") (pintype "bidirectional"))
    )
    (net (code "64") (name "Net-(TQFP-32-UCAP)") (class "Default")
      (node (ref "C34") (pin "2") (pinfunction "2_2") (pintype "passive"))
      (node (ref "SJ31") (pin "2") (pinfunction "2_2") (pintype "passive"))
      (node (ref "SV8") (pin "3") (pinfunction "3_3") (pintype "passive"))
      (node (ref "TQFP-32") (pin "27") (pinfunction "UCAP_27") (pintype "output"))
    )
    (net (code "65") (name "Net-(TQFP-32-UGND)") (class "Default")
      (node (ref "C35") (pin "2") (pinfunction "2_2") (pintype "passive"))
      (node (ref "SJ32") (pin "2") (pinfunction "2_2") (pintype "passive"))
      (node (ref "SV8") (pin "4") (pinfunction "4_4") (pintype "passive"))
      (node (ref "TQFP-32") (pin "28") (pinfunction "UGND_28") (pintype "passive"))
    )
    (net (code "66") (name "Net-(TQFP-32-UVCC)") (class "Default")
      (node (ref "C38") (pin "2") (pinfunction "2_2") (pintype "passive"))
      (node (ref "SJ35") (pin "2") (pinfunction "2_2") (pintype "passive"))
      (node (ref "SV8") (pin "7") (pinfunction "7_7") (pintype "passive"))
      (node (ref "TQFP-32") (pin "31") (pinfunction "UVCC_31") (pintype "power_in"))
    )
    (net (code "67") (name "Net-(TQFP-32-VCC)") (class "Default")
      (node (ref "C20") (pin "2") (pinfunction "2_2") (pintype "passive"))
      (node (ref "SJ17") (pin "2") (pinfunction "2_2") (pintype "passive"))
      (node (ref "SV16") (pin "4") (pinfunction "4_4") (pintype "passive"))
      (node (ref "TQFP-32") (pin "4") (pinfunction "VCC_4") (pintype "power_in"))
    )
    (net (code "68") (name "Net-(TQFP-32-XTAL1)") (class "Default")
      (node (ref "C25") (pin "2") (pinfunction "2_2") (pintype "passive"))
      (node (ref "SJ20") (pin "2") (pinfunction "2_2") (pintype "passive"))
      (node (ref "SV16") (pin "1") (pinfunction "1_1") (pintype "passive"))
      (node (ref "TQFP-32") (pin "1") (pinfunction "XTAL1_1") (pintype "input"))
    )
    (net (code "69") (name "Net-(TQFP-32-~{RESET_(PC1_{slash}_DW}))") (class "Default")
      (node (ref "C31") (pin "2") (pinfunction "2_2") (pintype "passive"))
      (node (ref "SJ28") (pin "2") (pinfunction "2_2") (pintype "passive"))
      (node (ref "SV4") (pin "8") (pinfunction "8_8") (pintype "passive"))
      (node (ref "TQFP-32") (pin "24") (pinfunction "~{RESET_(PC1_/_DW})_24") (pintype "bidirectional"))
    )
    (net (code "70") (name "Net-(TQFP-44-AVCC)") (class "Default")
      (node (ref "TQFP-44") (pin "39") (pinfunction "AVCC_39") (pintype "power_in"))
      (node (ref "U$1") (pin "6") (pinfunction "6_6") (pintype "passive"))
    )
    (net (code "71") (name "Net-(TQFP-44-GND)") (class "Default")
      (node (ref "TQFP-44") (pin "8") (pinfunction "GND_8") (pintype "power_in"))
      (node (ref "U$6") (pin "8") (pinfunction "8_8") (pintype "passive"))
    )
    (net (code "72") (name "Net-(TQFP-44-GND1)") (class "Default")
      (node (ref "TQFP-44") (pin "18") (pinfunction "GND1_18") (pintype "power_in"))
      (node (ref "U$5") (pin "7") (pinfunction "7_7") (pintype "passive"))
    )
    (net (code "73") (name "Net-(TQFP-44-GND2)") (class "Default")
      (node (ref "TQFP-44") (pin "30") (pinfunction "GND2_30") (pintype "power_in"))
      (node (ref "U$2") (pin "8") (pinfunction "8_8") (pintype "passive"))
    )
    (net (code "74") (name "Net-(TQFP-44-GND3)") (class "Default")
      (node (ref "TQFP-44") (pin "38") (pinfunction "GND3_38") (pintype "power_in"))
      (node (ref "U$1") (pin "5") (pinfunction "5_5") (pintype "passive"))
    )
    (net (code "75") (name "Net-(TQFP-44-PA0)") (class "Default")
      (node (ref "TQFP-44") (pin "40") (pinfunction "PA0_40") (pintype "bidirectional"))
      (node (ref "U$1") (pin "7") (pinfunction "7_7") (pintype "passive"))
    )
    (net (code "76") (name "Net-(TQFP-44-PA1)") (class "Default")
      (node (ref "TQFP-44") (pin "41") (pinfunction "PA1_41") (pintype "bidirectional"))
      (node (ref "U$1") (pin "8") (pinfunction "8_8") (pintype "passive"))
    )
    (net (code "77") (name "Net-(TQFP-44-PA2)") (class "Default")
      (node (ref "TQFP-44") (pin "42") (pinfunction "PA2_42") (pintype "bidirectional"))
      (node (ref "U$1") (pin "9") (pinfunction "9_9") (pintype "passive"))
    )
    (net (code "78") (name "Net-(TQFP-44-PA3)") (class "Default")
      (node (ref "TQFP-44") (pin "43") (pinfunction "PA3_43") (pintype "bidirectional"))
      (node (ref "U$1") (pin "10") (pinfunction "10_10") (pintype "passive"))
    )
    (net (code "79") (name "Net-(TQFP-44-PA4)") (class "Default")
      (node (ref "TQFP-44") (pin "44") (pinfunction "PA4_44") (pintype "bidirectional"))
      (node (ref "U$1") (pin "11") (pinfunction "11_11") (pintype "passive"))
    )
    (net (code "80") (name "Net-(TQFP-44-PA5)") (class "Default")
      (node (ref "TQFP-44") (pin "1") (pinfunction "PA5_1") (pintype "bidirectional"))
      (node (ref "U$6") (pin "1") (pinfunction "1_1") (pintype "passive"))
    )
    (net (code "81") (name "Net-(TQFP-44-PA6)") (class "Default")
      (node (ref "TQFP-44") (pin "2") (pinfunction "PA6_2") (pintype "bidirectional"))
      (node (ref "U$6") (pin "2") (pinfunction "2_2") (pintype "passive"))
    )
    (net (code "82") (name "Net-(TQFP-44-PA7)") (class "Default")
      (node (ref "TQFP-44") (pin "3") (pinfunction "PA7_3") (pintype "bidirectional"))
      (node (ref "U$6") (pin "3") (pinfunction "3_3") (pintype "passive"))
    )
    (net (code "83") (name "Net-(TQFP-44-PB0)") (class "Default")
      (node (ref "TQFP-44") (pin "4") (pinfunction "PB0_4") (pintype "bidirectional"))
      (node (ref "U$6") (pin "4") (pinfunction "4_4") (pintype "passive"))
    )
    (net (code "84") (name "Net-(TQFP-44-PB1)") (class "Default")
      (node (ref "TQFP-44") (pin "5") (pinfunction "PB1_5") (pintype "bidirectional"))
      (node (ref "U$6") (pin "5") (pinfunction "5_5") (pintype "passive"))
    )
    (net (code "85") (name "Net-(TQFP-44-PB2)") (class "Default")
      (node (ref "TQFP-44") (pin "6") (pinfunction "PB2_6") (pintype "bidirectional"))
      (node (ref "U$6") (pin "6") (pinfunction "6_6") (pintype "passive"))
    )
    (net (code "86") (name "Net-(TQFP-44-PB3)") (class "Default")
      (node (ref "TQFP-44") (pin "7") (pinfunction "PB3_7") (pintype "bidirectional"))
      (node (ref "U$6") (pin "7") (pinfunction "7_7") (pintype "passive"))
    )
    (net (code "87") (name "Net-(TQFP-44-PC0)") (class "Default")
      (node (ref "TQFP-44") (pin "10") (pinfunction "PC0_10") (pintype "bidirectional"))
      (node (ref "U$6") (pin "10") (pinfunction "10_10") (pintype "passive"))
    )
    (net (code "88") (name "Net-(TQFP-44-PC1)") (class "Default")
      (node (ref "TQFP-44") (pin "11") (pinfunction "PC1_11") (pintype "bidirectional"))
      (node (ref "U$6") (pin "11") (pinfunction "11_11") (pintype "passive"))
    )
    (net (code "89") (name "Net-(TQFP-44-PC2)") (class "Default")
      (node (ref "TQFP-44") (pin "12") (pinfunction "PC2_12") (pintype "bidirectional"))
      (node (ref "U$5") (pin "1") (pinfunction "1_1") (pintype "passive"))
    )
    (net (code "90") (name "Net-(TQFP-44-PC3)") (class "Default")
      (node (ref "TQFP-44") (pin "13") (pinfunction "PC3_13") (pintype "bidirectional"))
      (node (ref "U$5") (pin "2") (pinfunction "2_2") (pintype "passive"))
    )
    (net (code "91") (name "Net-(TQFP-44-PC4)") (class "Default")
      (node (ref "TQFP-44") (pin "14") (pinfunction "PC4_14") (pintype "bidirectional"))
      (node (ref "U$5") (pin "3") (pinfunction "3_3") (pintype "passive"))
    )
    (net (code "92") (name "Net-(TQFP-44-PC5)") (class "Default")
      (node (ref "TQFP-44") (pin "15") (pinfunction "PC5_15") (pintype "bidirectional"))
      (node (ref "U$5") (pin "4") (pinfunction "4_4") (pintype "passive"))
    )
    (net (code "93") (name "Net-(TQFP-44-PC6)") (class "Default")
      (node (ref "TQFP-44") (pin "16") (pinfunction "PC6_16") (pintype "bidirectional"))
      (node (ref "U$5") (pin "5") (pinfunction "5_5") (pintype "passive"))
    )
    (net (code "94") (name "Net-(TQFP-44-PC7)") (class "Default")
      (node (ref "TQFP-44") (pin "17") (pinfunction "PC7_17") (pintype "bidirectional"))
      (node (ref "U$5") (pin "6") (pinfunction "6_6") (pintype "passive"))
    )
    (net (code "95") (name "Net-(TQFP-44-PD0)") (class "Default")
      (node (ref "TQFP-44") (pin "20") (pinfunction "PD0_20") (pintype "bidirectional"))
      (node (ref "U$5") (pin "9") (pinfunction "9_9") (pintype "passive"))
    )
    (net (code "96") (name "Net-(TQFP-44-PD1)") (class "Default")
      (node (ref "TQFP-44") (pin "21") (pinfunction "PD1_21") (pintype "bidirectional"))
      (node (ref "U$5") (pin "10") (pinfunction "10_10") (pintype "passive"))
    )
    (net (code "97") (name "Net-(TQFP-44-PD2)") (class "Default")
      (node (ref "TQFP-44") (pin "22") (pinfunction "PD2_22") (pintype "bidirectional"))
      (node (ref "U$5") (pin "11") (pinfunction "11_11") (pintype "passive"))
    )
    (net (code "98") (name "Net-(TQFP-44-PD3)") (class "Default")
      (node (ref "TQFP-44") (pin "23") (pinfunction "PD3_23") (pintype "bidirectional"))
      (node (ref "U$2") (pin "1") (pinfunction "1_1") (pintype "passive"))
    )
    (net (code "99") (name "Net-(TQFP-44-PD4)") (class "Default")
      (node (ref "TQFP-44") (pin "24") (pinfunction "PD4_24") (pintype "bidirectional"))
      (node (ref "U$2") (pin "2") (pinfunction "2_2") (pintype "passive"))
    )
    (net (code "100") (name "Net-(TQFP-44-PD5)") (class "Default")
      (node (ref "TQFP-44") (pin "25") (pinfunction "PD5_25") (pintype "bidirectional"))
      (node (ref "U$2") (pin "3") (pinfunction "3_3") (pintype "passive"))
    )
    (net (code "101") (name "Net-(TQFP-44-PD6)") (class "Default")
      (node (ref "TQFP-44") (pin "26") (pinfunction "PD6_26") (pintype "bidirectional"))
      (node (ref "U$2") (pin "4") (pinfunction "4_4") (pintype "passive"))
    )
    (net (code "102") (name "Net-(TQFP-44-PD7)") (class "Default")
      (node (ref "TQFP-44") (pin "27") (pinfunction "PD7_27") (pintype "bidirectional"))
      (node (ref "U$2") (pin "5") (pinfunction "5_5") (pintype "passive"))
    )
    (net (code "103") (name "Net-(TQFP-44-PDI_DATA)") (class "Default")
      (node (ref "TQFP-44") (pin "34") (pinfunction "PDI_DATA_34") (pintype "bidirectional"))
      (node (ref "U$1") (pin "1") (pinfunction "1_1") (pintype "passive"))
    )
    (net (code "104") (name "Net-(TQFP-44-PE0)") (class "Default")
      (node (ref "TQFP-44") (pin "28") (pinfunction "PE0_28") (pintype "bidirectional"))
      (node (ref "U$2") (pin "6") (pinfunction "6_6") (pintype "passive"))
    )
    (net (code "105") (name "Net-(TQFP-44-PE1)") (class "Default")
      (node (ref "TQFP-44") (pin "29") (pinfunction "PE1_29") (pintype "bidirectional"))
      (node (ref "U$2") (pin "7") (pinfunction "7_7") (pintype "passive"))
    )
    (net (code "106") (name "Net-(TQFP-44-PE2)") (class "Default")
      (node (ref "TQFP-44") (pin "32") (pinfunction "PE2_32") (pintype "bidirectional"))
      (node (ref "U$2") (pin "10") (pinfunction "10_10") (pintype "passive"))
    )
    (net (code "107") (name "Net-(TQFP-44-PE3)") (class "Default")
      (node (ref "TQFP-44") (pin "33") (pinfunction "PE3_33") (pintype "bidirectional"))
      (node (ref "U$2") (pin "11") (pinfunction "11_11") (pintype "passive"))
    )
    (net (code "108") (name "Net-(TQFP-44-PR0(XT2))") (class "Default")
      (node (ref "TQFP-44") (pin "36") (pinfunction "PR0(XT2)_36") (pintype "bidirectional"))
      (node (ref "U$1") (pin "3") (pinfunction "3_3") (pintype "passive"))
    )
    (net (code "109") (name "Net-(TQFP-44-PR1(XT1))") (class "Default")
      (node (ref "TQFP-44") (pin "37") (pinfunction "PR1(XT1)_37") (pintype "bidirectional"))
      (node (ref "U$1") (pin "4") (pinfunction "4_4") (pintype "passive"))
    )
    (net (code "110") (name "Net-(TQFP-44-VCC)") (class "Default")
      (node (ref "TQFP-44") (pin "9") (pinfunction "VCC_9") (pintype "power_in"))
      (node (ref "U$6") (pin "9") (pinfunction "9_9") (pintype "passive"))
    )
    (net (code "111") (name "Net-(TQFP-44-VCC1)") (class "Default")
      (node (ref "TQFP-44") (pin "19") (pinfunction "VCC1_19") (pintype "power_in"))
      (node (ref "U$5") (pin "8") (pinfunction "8_8") (pintype "passive"))
    )
    (net (code "112") (name "Net-(TQFP-44-VCC2)") (class "Default")
      (node (ref "TQFP-44") (pin "31") (pinfunction "VCC2_31") (pintype "power_in"))
      (node (ref "U$2") (pin "9") (pinfunction "9_9") (pintype "passive"))
    )
    (net (code "113") (name "Net-(TQFP-44-~{RESET}{slash}PDI_CLK)") (class "Default")
      (node (ref "TQFP-44") (pin "35") (pinfunction "~{RESET}/PDI_CLK_35") (pintype "bidirectional"))
      (node (ref "U$1") (pin "2") (pinfunction "2_2") (pintype "passive"))
    )
  )
)
